# L.net
KiCad netlist of a schematic drawn in Altium Designer
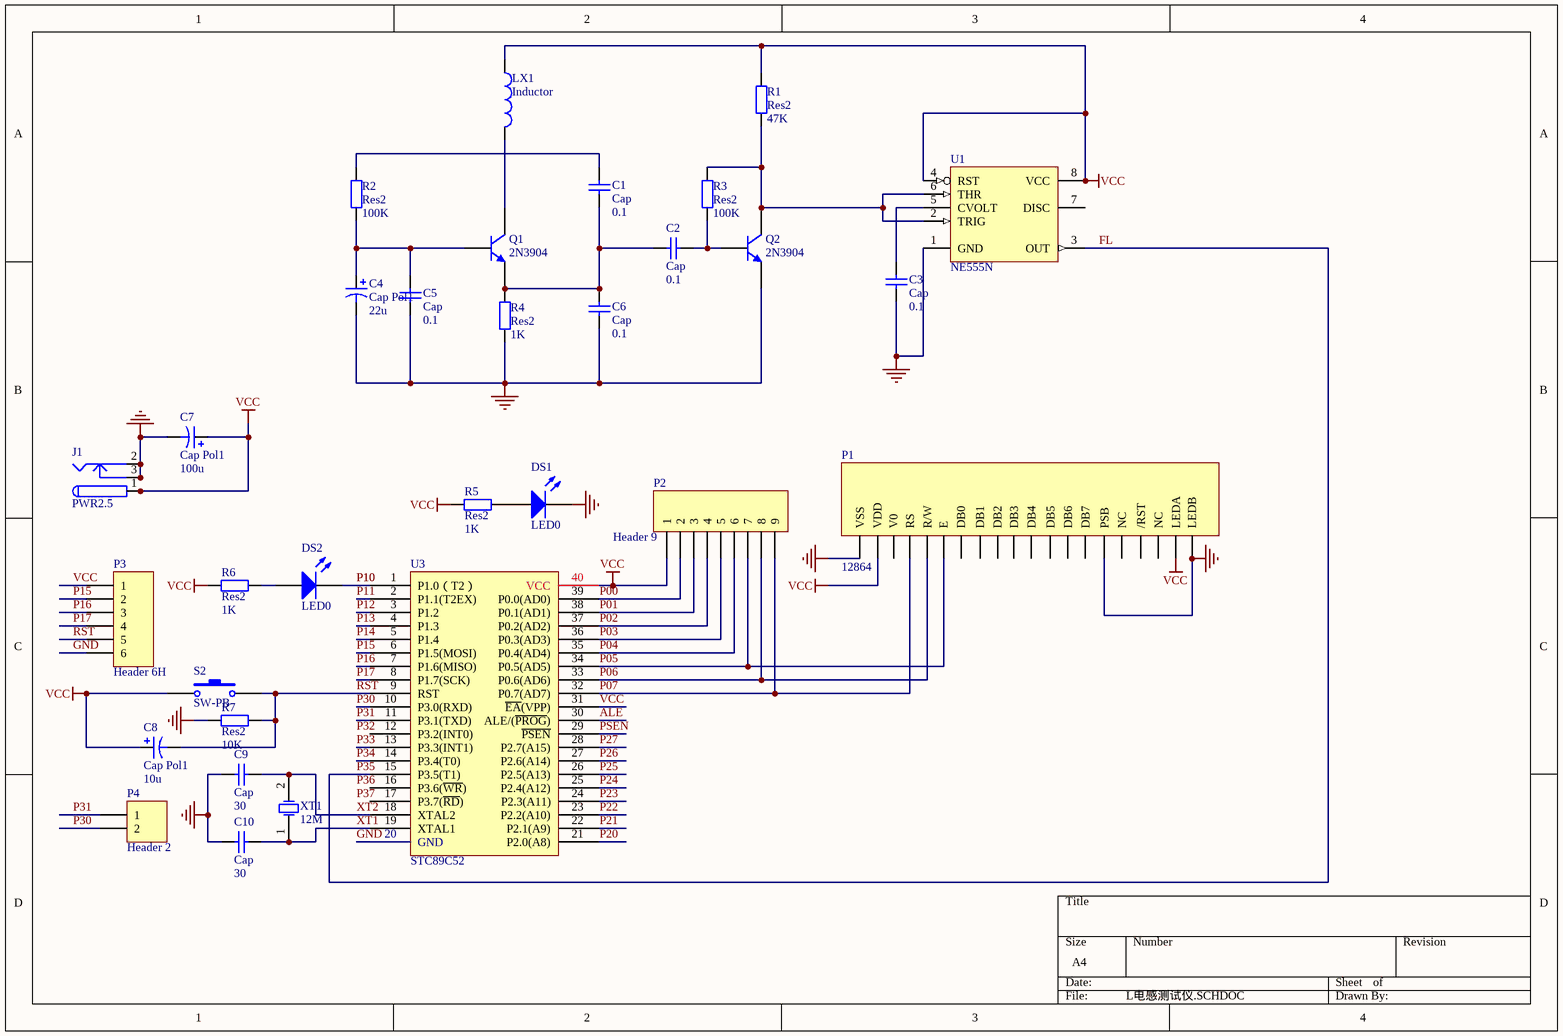
[diagram p0: L电感测试仪.SCHDOC]

(export (version "E")
  (design (tool "Eeschema 10.0.6"))
  (components
    (comp (ref "C1")
      (value "Cap")
      (footprint "RAD-0.2")
      (description "Capacitor")
      (fields (field (name "ALTIUM_VALUE") "0.1") (field (name "PUBLISHER") "Altium Limited"))
      (libsource (lib "Miscellaneous Devices") (part "Cap"))
    )
    (comp (ref "C2")
      (value "Cap")
      (footprint "RAD-0.2")
      (description "Capacitor")
      (fields (field (name "ALTIUM_VALUE") "0.1") (field (name "PUBLISHER") "Altium Limited"))
      (libsource (lib "Miscellaneous Devices") (part "Cap"))
    )
    (comp (ref "C3")
      (value "Cap")
      (footprint "RAD-0.2")
      (description "Capacitor")
      (fields (field (name "ALTIUM_VALUE") "0.1") (field (name "PUBLISHER") "Altium Limited"))
      (libsource (lib "Miscellaneous Devices") (part "Cap"))
    )
    (comp (ref "C4")
      (value "Cap Pol1")
      (footprint "电容")
      (description "Polarized Capacitor (Radial)")
      (fields (field (name "ALTIUM_VALUE") "22u") (field (name "PUBLISHER") "Altium Limited"))
      (libsource (lib "Miscellaneous Devices") (part "Cap Pol1"))
    )
    (comp (ref "C5")
      (value "Cap")
      (footprint "RAD-0.2")
      (description "Capacitor")
      (fields (field (name "ALTIUM_VALUE") "0.1") (field (name "PUBLISHER") "Altium Limited"))
      (libsource (lib "Miscellaneous Devices") (part "Cap"))
    )
    (comp (ref "C6")
      (value "Cap")
      (footprint "RAD-0.2")
      (description "Capacitor")
      (fields (field (name "ALTIUM_VALUE") "0.1") (field (name "PUBLISHER") "Altium Limited"))
      (libsource (lib "Miscellaneous Devices") (part "Cap"))
    )
    (comp (ref "C7")
      (value "Cap Pol1")
      (footprint "电容")
      (description "Polarized Capacitor (Radial)")
      (fields (field (name "ALTIUM_VALUE") "100u") (field (name "PUBLISHER") "Altium Limited"))
      (libsource (lib "Miscellaneous Devices") (part "Cap Pol1"))
    )
    (comp (ref "C8")
      (value "Cap Pol1")
      (footprint "电容")
      (description "Polarized Capacitor (Radial)")
      (fields (field (name "ALTIUM_VALUE") "10u") (field (name "PUBLISHER") "Altium Limited"))
      (libsource (lib "Miscellaneous Devices") (part "Cap Pol1"))
    )
    (comp (ref "C9")
      (value "Cap")
      (footprint "RAD-0.1")
      (description "Capacitor")
      (fields (field (name "ALTIUM_VALUE") "30") (field (name "PUBLISHER") "Altium Limited"))
      (libsource (lib "Miscellaneous Devices") (part "Cap"))
    )
    (comp (ref "C10")
      (value "Cap")
      (footprint "RAD-0.1")
      (description "Capacitor")
      (fields (field (name "ALTIUM_VALUE") "30") (field (name "PUBLISHER") "Altium Limited"))
      (libsource (lib "Miscellaneous Devices") (part "Cap"))
    )
    (comp (ref "DS1")
      (value "LED0")
      (footprint "RAD-0.1")
      (description "Typical INFRARED GaAs LED")
      (fields (field (name "PUBLISHER") "Altium Limited"))
      (libsource (lib "Miscellaneous Devices") (part "LED0"))
    )
    (comp (ref "DS2")
      (value "LED0")
      (footprint "RAD-0.1")
      (description "Typical INFRARED GaAs LED")
      (fields (field (name "PUBLISHER") "Altium Limited"))
      (libsource (lib "Miscellaneous Devices") (part "LED0"))
    )
    (comp (ref "J1")
      (value "PWR2.5")
      (footprint "KLD-0202")
      (description "Low Voltage Power Supply Connector")
      (fields (field (name "PUBLISHER") "Altium Limited"))
      (libsource (lib "Miscellaneous Connectors") (part "PWR2.5"))
    )
    (comp (ref "LX1")
      (value "Inductor")
      (footprint "RAD-0.3")
      (fields (field (name "PUBLISHER") "Altium Limited"))
      (libsource (lib "Miscellaneous Devices") (part "Inductor"))
    )
    (comp (ref "P1") (value "12864") (footprint "HDR1X20") (libsource (lib "我的原理图库.") (part "12864")))
    (comp (ref "P2")
      (value "Header 9")
      (footprint "HDR1X9")
      (description "Header, 9-Pin")
      (fields (field (name "PUBLISHER") "Altium Limited"))
      (libsource (lib "Miscellaneous Connectors") (part "Header 9"))
    )
    (comp (ref "P3")
      (value "Header 6H")
      (footprint "HDR1X6")
      (description "Header, 6-Pin, Right Angle")
      (fields (field (name "PUBLISHER") "Altium Limited"))
      (libsource (lib "Miscellaneous Connectors") (part "Header 6H"))
    )
    (comp (ref "P4")
      (value "Header 2")
      (footprint "HDR1X2")
      (description "Header, 2-Pin")
      (fields (field (name "PUBLISHER") "Altium Limited"))
      (libsource (lib "Miscellaneous Connectors") (part "Header 2"))
    )
    (comp (ref "Q1")
      (value "2N3904")
      (footprint "BCY-W3/E4")
      (description "NPN General Purpose Amplifier")
      (fields (field (name "PUBLISHER") "Altium Limited"))
      (libsource (lib "Miscellaneous Devices") (part "2N3904"))
    )
    (comp (ref "Q2")
      (value "2N3904")
      (footprint "BCY-W3/E4")
      (description "NPN General Purpose Amplifier")
      (fields (field (name "PUBLISHER") "Altium Limited"))
      (libsource (lib "Miscellaneous Devices") (part "2N3904"))
    )
    (comp (ref "R1")
      (value "Res2")
      (footprint "AXIAL-0.4")
      (description "Resistor")
      (fields (field (name "ALTIUM_VALUE") "47K") (field (name "PUBLISHER") "Altium Limited"))
      (libsource (lib "Miscellaneous Devices") (part "Res2"))
    )
    (comp (ref "R2")
      (value "Res2")
      (footprint "AXIAL-0.4")
      (description "Resistor")
      (fields (field (name "ALTIUM_VALUE") "100K") (field (name "PUBLISHER") "Altium Limited"))
      (libsource (lib "Miscellaneous Devices") (part "Res2"))
    )
    (comp (ref "R3")
      (value "Res2")
      (footprint "AXIAL-0.4")
      (description "Resistor")
      (fields (field (name "ALTIUM_VALUE") "100K") (field (name "PUBLISHER") "Altium Limited"))
      (libsource (lib "") (part "Res2_1"))
    )
    (comp (ref "R4")
      (value "Res2")
      (footprint "AXIAL-0.4")
      (description "Resistor")
      (fields (field (name "ALTIUM_VALUE") "1K") (field (name "PUBLISHER") "Altium Limited"))
      (libsource (lib "Miscellaneous Devices") (part "Res2"))
    )
    (comp (ref "R5")
      (value "Res2")
      (footprint "AXIAL-0.4")
      (description "Resistor")
      (fields (field (name "ALTIUM_VALUE") "1K") (field (name "PUBLISHER") "Altium Limited"))
      (libsource (lib "") (part "Res2_3"))
    )
    (comp (ref "R6")
      (value "Res2")
      (footprint "AXIAL-0.4")
      (description "Resistor")
      (fields (field (name "ALTIUM_VALUE") "1K") (field (name "PUBLISHER") "Altium Limited"))
      (libsource (lib "") (part "Res2_2"))
    )
    (comp (ref "R7")
      (value "Res2")
      (footprint "AXIAL-0.4")
      (description "Resistor")
      (fields (field (name "ALTIUM_VALUE") "10K") (field (name "PUBLISHER") "Altium Limited"))
      (libsource (lib "") (part "Res2_3"))
    )
    (comp (ref "S2")
      (value "SW-PB")
      (footprint "点动按键")
      (description "Switch")
      (fields (field (name "PUBLISHER") "Altium Limited"))
      (libsource (lib "Miscellaneous Devices") (part "SW-PB"))
    )
    (comp (ref "U1")
      (value "NE555N")
      (footprint "DIP8")
      (description "General-Purpose Single Bipolar Timer")
      (fields (field (name "PUBLISHER") "Altium Limited"))
      (libsource (lib "ST Analog Timer Circuit") (part "NE555N"))
    )
    (comp (ref "U3")
      (value "STC89C52")
      (footprint "AT89S52")
      (libsource (lib "原理图lanzhengfaSchlib1") (part "AT89S52"))
    )
    (comp (ref "XT1") (value "12M") (footprint "圆晶振") (libsource (lib "原理图lanzhengfaSchlib1") (part "XTAL2")))
  )
  (nets
    (net (code "1") (name "/ALE") (class "Default")
      (node (ref "U3") (pin "30") (pinfunction "ALE/(~{PROG})_30") (pintype "passive"))
    )
    (net (code "2") (name "/FL") (class "Default")
      (node (ref "U1") (pin "3") (pinfunction "OUT_3") (pintype "output"))
      (node (ref "U3") (pin "15") (pinfunction "P3.5(T1)_15") (pintype "passive"))
    )
    (net (code "3") (name "/P00") (class "Default")
      (node (ref "P2") (pin "2") (pinfunction "2_2") (pintype "passive"))
      (node (ref "U3") (pin "39") (pinfunction "P0.0(AD0)_39") (pintype "passive"))
    )
    (net (code "4") (name "/P01") (class "Default")
      (node (ref "P2") (pin "3") (pinfunction "3_3") (pintype "passive"))
      (node (ref "U3") (pin "38") (pinfunction "P0.1(AD1)_38") (pintype "passive"))
    )
    (net (code "5") (name "/P02") (class "Default")
      (node (ref "P2") (pin "4") (pinfunction "4_4") (pintype "passive"))
      (node (ref "U3") (pin "37") (pinfunction "P0.2(AD2)_37") (pintype "passive"))
    )
    (net (code "6") (name "/P03") (class "Default")
      (node (ref "P2") (pin "5") (pinfunction "5_5") (pintype "passive"))
      (node (ref "U3") (pin "36") (pinfunction "P0.3(AD3)_36") (pintype "passive"))
    )
    (net (code "7") (name "/P04") (class "Default")
      (node (ref "P2") (pin "6") (pinfunction "6_6") (pintype "passive"))
      (node (ref "U3") (pin "35") (pinfunction "P0.4(AD4)_35") (pintype "passive"))
    )
    (net (code "8") (name "/P05") (class "Default")
      (node (ref "P1") (pin "6") (pinfunction "E_6") (pintype "passive"))
      (node (ref "P2") (pin "7") (pinfunction "7_7") (pintype "passive"))
      (node (ref "U3") (pin "34") (pinfunction "P0.5(AD5)_34") (pintype "passive"))
    )
    (net (code "9") (name "/P06") (class "Default")
      (node (ref "P1") (pin "5") (pinfunction "R/W_5") (pintype "passive"))
      (node (ref "P2") (pin "8") (pinfunction "8_8") (pintype "passive"))
      (node (ref "U3") (pin "33") (pinfunction "P0.6(AD6)_33") (pintype "passive"))
    )
    (net (code "10") (name "/P07") (class "Default")
      (node (ref "P1") (pin "4") (pinfunction "RS_4") (pintype "passive"))
      (node (ref "P2") (pin "9") (pinfunction "9_9") (pintype "passive"))
      (node (ref "U3") (pin "32") (pinfunction "P0.7(AD7)_32") (pintype "passive"))
    )
    (net (code "11") (name "/P10") (class "Default")
      (node (ref "DS2") (pin "2") (pinfunction "K_2") (pintype "passive"))
      (node (ref "U3") (pin "1") (pinfunction "P1.0（T2）_1") (pintype "passive"))
    )
    (net (code "12") (name "/P11") (class "Default")
      (node (ref "U3") (pin "2") (pinfunction "P1.1(T2EX)_2") (pintype "passive"))
    )
    (net (code "13") (name "/P12") (class "Default")
      (node (ref "U3") (pin "3") (pinfunction "P1.2_3") (pintype "passive"))
    )
    (net (code "14") (name "/P13") (class "Default")
      (node (ref "U3") (pin "4") (pinfunction "P1.3_4") (pintype "passive"))
    )
    (net (code "15") (name "/P14") (class "Default")
      (node (ref "U3") (pin "5") (pinfunction "P1.4_5") (pintype "passive"))
    )
    (net (code "16") (name "/P15") (class "Default")
      (node (ref "P3") (pin "2") (pinfunction "2_2") (pintype "passive"))
      (node (ref "U3") (pin "6") (pinfunction "P1.5(MOSI)_6") (pintype "passive"))
    )
    (net (code "17") (name "/P16") (class "Default")
      (node (ref "P3") (pin "3") (pinfunction "3_3") (pintype "passive"))
      (node (ref "U3") (pin "7") (pinfunction "P1.6(MISO)_7") (pintype "passive"))
    )
    (net (code "18") (name "/P17") (class "Default")
      (node (ref "P3") (pin "4") (pinfunction "4_4") (pintype "passive"))
      (node (ref "U3") (pin "8") (pinfunction "P1.7(SCK)_8") (pintype "passive"))
    )
    (net (code "19") (name "/P20") (class "Default")
      (node (ref "U3") (pin "21") (pinfunction "P2.0(A8)_21") (pintype "passive"))
    )
    (net (code "20") (name "/P21") (class "Default")
      (node (ref "U3") (pin "22") (pinfunction "P2.1(A9)_22") (pintype "passive"))
    )
    (net (code "21") (name "/P22") (class "Default")
      (node (ref "U3") (pin "23") (pinfunction "P2.2(A10)_23") (pintype "passive"))
    )
    (net (code "22") (name "/P23") (class "Default")
      (node (ref "U3") (pin "24") (pinfunction "P2.3(A11)_24") (pintype "passive"))
    )
    (net (code "23") (name "/P24") (class "Default")
      (node (ref "U3") (pin "25") (pinfunction "P2.4(A12)_25") (pintype "passive"))
    )
    (net (code "24") (name "/P25") (class "Default")
      (node (ref "U3") (pin "26") (pinfunction "P2.5(A13)_26") (pintype "passive"))
    )
    (net (code "25") (name "/P26") (class "Default")
      (node (ref "U3") (pin "27") (pinfunction "P2.6(A14)_27") (pintype "passive"))
    )
    (net (code "26") (name "/P27") (class "Default")
      (node (ref "U3") (pin "28") (pinfunction "P2.7(A15)_28") (pintype "passive"))
    )
    (net (code "27") (name "/P30") (class "Default")
      (node (ref "P4") (pin "2") (pinfunction "2_2") (pintype "passive"))
      (node (ref "U3") (pin "10") (pinfunction "P3.0(RXD)_10") (pintype "passive"))
    )
    (net (code "28") (name "/P31") (class "Default")
      (node (ref "P4") (pin "1") (pinfunction "1_1") (pintype "passive"))
      (node (ref "U3") (pin "11") (pinfunction "P3.1(TXD)_11") (pintype "passive"))
    )
    (net (code "30") (name "/P33") (class "Default")
      (node (ref "U3") (pin "13") (pinfunction "P3.3(INT1)_13") (pintype "passive"))
    )
    (net (code "31") (name "/P34") (class "Default")
      (node (ref "U3") (pin "14") (pinfunction "P3.4(T0)_14") (pintype "passive"))
    )
    (net (code "34") (name "/PSEN") (class "Default")
      (node (ref "U3") (pin "29") (pinfunction "~{PSEN}_29") (pintype "passive"))
    )
    (net (code "35") (name "/RST") (class "Default")
      (node (ref "C8") (pin "2") (pinfunction "2_2") (pintype "passive"))
      (node (ref "P3") (pin "5") (pinfunction "5_5") (pintype "passive"))
      (node (ref "R7") (pin "2") (pinfunction "2_2") (pintype "passive"))
      (node (ref "S2") (pin "2") (pinfunction "2_2") (pintype "passive"))
      (node (ref "U3") (pin "9") (pinfunction "RST_9") (pintype "passive"))
    )
    (net (code "36") (name "/XT1") (class "Default")
      (node (ref "C10") (pin "2") (pinfunction "2_2") (pintype "passive"))
      (node (ref "U3") (pin "19") (pinfunction "XTAL1_19") (pintype "passive"))
      (node (ref "XT1") (pin "1") (pinfunction "OSC1_1") (pintype "passive"))
    )
    (net (code "37") (name "/XT2") (class "Default")
      (node (ref "C9") (pin "2") (pinfunction "2_2") (pintype "passive"))
      (node (ref "U3") (pin "18") (pinfunction "XTAL2_18") (pintype "passive"))
      (node (ref "XT1") (pin "2") (pinfunction "OSC2_2") (pintype "passive"))
    )
    (net (code "38") (name "GND") (class "Default")
      (node (ref "C10") (pin "1") (pinfunction "1_1") (pintype "passive"))
      (node (ref "C3") (pin "2") (pinfunction "2_2") (pintype "passive"))
      (node (ref "C4") (pin "2") (pinfunction "2_2") (pintype "passive"))
      (node (ref "C5") (pin "1") (pinfunction "1_1") (pintype "passive"))
      (node (ref "C6") (pin "1") (pinfunction "1_1") (pintype "passive"))
      (node (ref "C7") (pin "2") (pinfunction "2_2") (pintype "passive"))
      (node (ref "C9") (pin "1") (pinfunction "1_1") (pintype "passive"))
      (node (ref "DS1") (pin "2") (pinfunction "K_2") (pintype "passive"))
      (node (ref "J1") (pin "2") (pinfunction "2_2") (pintype "power_in"))
      (node (ref "J1") (pin "2A") (pinfunction "2A_2A") (pintype "power_in"))
      (node (ref "J1") (pin "2B") (pinfunction "2B_2B") (pintype "power_in"))
      (node (ref "J1") (pin "3") (pinfunction "3_3") (pintype "power_in"))
      (node (ref "J1") (pin "3A") (pinfunction "3A_3A") (pintype "power_in"))
      (node (ref "J1") (pin "3B") (pinfunction "3B_3B") (pintype "power_in"))
      (node (ref "P1") (pin "1") (pinfunction "VSS_1") (pintype "passive"))
      (node (ref "P1") (pin "15") (pinfunction "PSB_15") (pintype "passive"))
      (node (ref "P1") (pin "20") (pinfunction "LEDB_20") (pintype "passive"))
      (node (ref "P3") (pin "6") (pinfunction "6_6") (pintype "passive"))
      (node (ref "Q2") (pin "1") (pinfunction "E_1") (pintype "passive"))
      (node (ref "R4") (pin "1") (pinfunction "1_1") (pintype "passive"))
      (node (ref "R7") (pin "1") (pinfunction "1_1") (pintype "passive"))
      (node (ref "U1") (pin "1") (pinfunction "GND_1") (pintype "power_in"))
      (node (ref "U3") (pin "20") (pinfunction "GND_20") (pintype "passive"))
    )
    (net (code "39") (name "Net-(C1-Pad2)") (class "Default")
      (node (ref "C1") (pin "2") (pinfunction "2_2") (pintype "passive"))
      (node (ref "R2") (pin "2") (pinfunction "2_2") (pintype "passive"))
    )
    (net (code "40") (name "Net-(DS1-A)") (class "Default")
      (node (ref "DS1") (pin "1") (pinfunction "A_1") (pintype "passive"))
      (node (ref "R5") (pin "2") (pinfunction "2_2") (pintype "passive"))
    )
    (net (code "41") (name "Net-(DS2-A)") (class "Default")
      (node (ref "DS2") (pin "1") (pinfunction "A_1") (pintype "passive"))
      (node (ref "R6") (pin "1") (pinfunction "1_1") (pintype "passive"))
    )
    (net (code "42") (name "Net-(Q1-B)") (class "Default")
      (node (ref "C4") (pin "1") (pinfunction "1_1") (pintype "passive"))
      (node (ref "C5") (pin "2") (pinfunction "2_2") (pintype "passive"))
      (node (ref "Q1") (pin "2") (pinfunction "B_2") (pintype "passive"))
      (node (ref "R2") (pin "1") (pinfunction "1_1") (pintype "passive"))
    )
    (net (code "43") (name "Net-(Q1-C)") (class "Default")
      (node (ref "LX1") (pin "2") (pinfunction "2_2") (pintype "passive"))
      (node (ref "Q1") (pin "3") (pinfunction "C_3") (pintype "passive"))
    )
    (net (code "44") (name "Net-(Q1-E)") (class "Default")
      (node (ref "C1") (pin "1") (pinfunction "1_1") (pintype "passive"))
      (node (ref "C2") (pin "2") (pinfunction "2_2") (pintype "passive"))
      (node (ref "C6") (pin "2") (pinfunction "2_2") (pintype "passive"))
      (node (ref "Q1") (pin "1") (pinfunction "E_1") (pintype "passive"))
      (node (ref "R4") (pin "2") (pinfunction "2_2") (pintype "passive"))
    )
    (net (code "45") (name "Net-(Q2-B)") (class "Default")
      (node (ref "C2") (pin "1") (pinfunction "1_1") (pintype "passive"))
      (node (ref "Q2") (pin "2") (pinfunction "B_2") (pintype "passive"))
      (node (ref "R3") (pin "2") (pinfunction "2_2") (pintype "passive"))
    )
    (net (code "46") (name "Net-(Q2-C)") (class "Default")
      (node (ref "Q2") (pin "3") (pinfunction "C_3") (pintype "passive"))
      (node (ref "R1") (pin "1") (pinfunction "1_1") (pintype "passive"))
      (node (ref "R3") (pin "1") (pinfunction "1_1") (pintype "passive"))
      (node (ref "U1") (pin "2") (pinfunction "TRIG_2") (pintype "input"))
      (node (ref "U1") (pin "6") (pinfunction "THR_6") (pintype "input"))
    )
    (net (code "47") (name "Net-(U1-CVOLT)") (class "Default")
      (node (ref "C3") (pin "1") (pinfunction "1_1") (pintype "passive"))
      (node (ref "U1") (pin "5") (pinfunction "CVOLT_5") (pintype "passive"))
    )
    (net (code "48") (name "VCC") (class "Default")
      (node (ref "C7") (pin "1") (pinfunction "1_1") (pintype "passive"))
      (node (ref "C8") (pin "1") (pinfunction "1_1") (pintype "passive"))
      (node (ref "J1") (pin "1") (pinfunction "1_1") (pintype "power_in"))
      (node (ref "J1") (pin "1A") (pinfunction "1A_1A") (pintype "power_in"))
      (node (ref "J1") (pin "1B") (pinfunction "1B_1B") (pintype "power_in"))
      (node (ref "LX1") (pin "1") (pinfunction "1_1") (pintype "passive"))
      (node (ref "P1") (pin "19") (pinfunction "LEDA_19") (pintype "passive"))
      (node (ref "P1") (pin "2") (pinfunction "VDD_2") (pintype "passive"))
      (node (ref "P2") (pin "1") (pinfunction "1_1") (pintype "passive"))
      (node (ref "P3") (pin "1") (pinfunction "1_1") (pintype "passive"))
      (node (ref "R1") (pin "2") (pinfunction "2_2") (pintype "passive"))
      (node (ref "R5") (pin "1") (pinfunction "1_1") (pintype "passive"))
      (node (ref "R6") (pin "2") (pinfunction "2_2") (pintype "passive"))
      (node (ref "S2") (pin "1") (pinfunction "1_1") (pintype "passive"))
      (node (ref "U1") (pin "4") (pinfunction "RST_4") (pintype "input"))
      (node (ref "U1") (pin "8") (pinfunction "VCC_8") (pintype "power_in"))
      (node (ref "U3") (pin "31") (pinfunction "~{EA}(VPP)_31") (pintype "passive"))
      (node (ref "U3") (pin "40") (pinfunction "VCC_40") (pintype "passive"))
    )
    (net (code "49") (name "unconnected-(P1-DB0-Pad7)") (class "Default")
      (node (ref "P1") (pin "7") (pinfunction "DB0_7") (pintype "passive"))
    )
    (net (code "50") (name "unconnected-(P1-DB1-Pad8)") (class "Default")
      (node (ref "P1") (pin "8") (pinfunction "DB1_8") (pintype "passive"))
    )
    (net (code "51") (name "unconnected-(P1-DB2-Pad9)") (class "Default")
      (node (ref "P1") (pin "9") (pinfunction "DB2_9") (pintype "passive"))
    )
    (net (code "52") (name "unconnected-(P1-DB3-Pad10)") (class "Default")
      (node (ref "P1") (pin "10") (pinfunction "DB3_10") (pintype "passive"))
    )
    (net (code "53") (name "unconnected-(P1-DB4-Pad11)") (class "Default")
      (node (ref "P1") (pin "11") (pinfunction "DB4_11") (pintype "passive"))
    )
    (net (code "54") (name "unconnected-(P1-DB5-Pad12)") (class "Default")
      (node (ref "P1") (pin "12") (pinfunction "DB5_12") (pintype "passive"))
    )
    (net (code "55") (name "unconnected-(P1-DB6-Pad13)") (class "Default")
      (node (ref "P1") (pin "13") (pinfunction "DB6_13") (pintype "passive"))
    )
    (net (code "56") (name "unconnected-(P1-DB7-Pad14)") (class "Default")
      (node (ref "P1") (pin "14") (pinfunction "DB7_14") (pintype "passive"))
    )
    (net (code "57") (name "unconnected-(P1-NC-Pad16)") (class "Default")
      (node (ref "P1") (pin "16") (pinfunction "NC_16") (pintype "passive"))
    )
    (net (code "58") (name "unconnected-(P1-NC-Pad18)") (class "Default")
      (node (ref "P1") (pin "18") (pinfunction "NC_18") (pintype "passive"))
    )
    (net (code "59") (name "unconnected-(P1-V0-Pad3)") (class "Default")
      (node (ref "P1") (pin "3") (pinfunction "V0_3") (pintype "passive"))
    )
    (net (code "60") (name "unconnected-(P1-{slash}RST-Pad17)") (class "Default")
      (node (ref "P1") (pin "17") (pinfunction "/RST_17") (pintype "passive"))
    )
    (net (code "61") (name "unconnected-(U1-DISC-Pad7)") (class "Default")
      (node (ref "U1") (pin "7") (pinfunction "DISC_7") (pintype "open_collector"))
    )
    (net (code "62") (name "unconnected-(U3-P3.2(INT0)-Pad12)") (class "Default")
      (node (ref "U3") (pin "12") (pinfunction "P3.2(INT0)_12") (pintype "passive"))
    )
    (net (code "63") (name "unconnected-(U3-P3.6(~{WR})-Pad16)") (class "Default")
      (node (ref "U3") (pin "16") (pinfunction "P3.6(~{WR})_16") (pintype "passive"))
    )
    (net (code "64") (name "unconnected-(U3-P3.7(~{RD})-Pad17)") (class "Default")
      (node (ref "U3") (pin "17") (pinfunction "P3.7(~{RD})_17") (pintype "passive"))
    )
  )
)
